# RgbwLedDriver.net
KiCad netlist of a schematic drawn in EAGLE
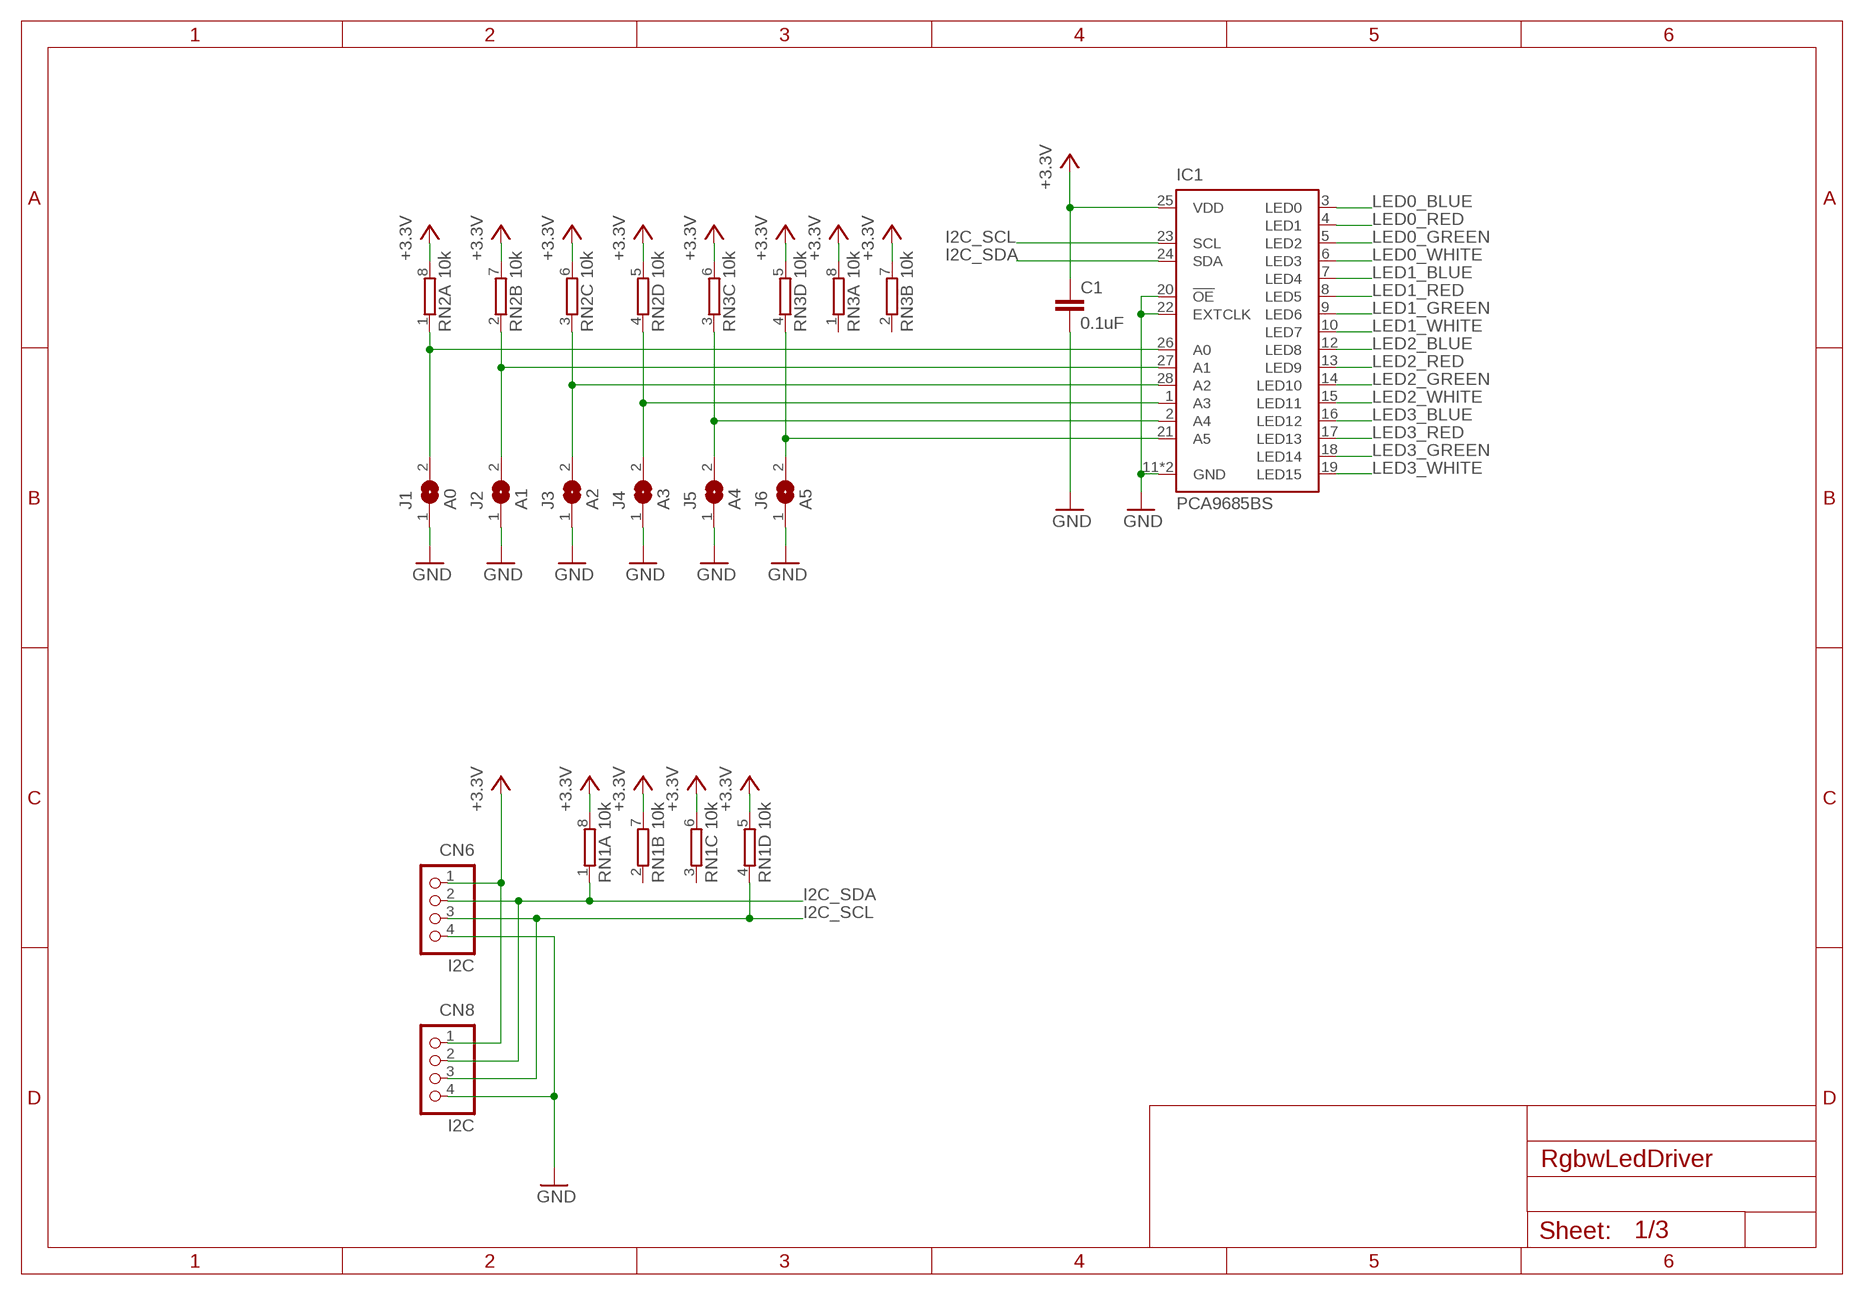
[diagram p0: schematic, sheet 1]
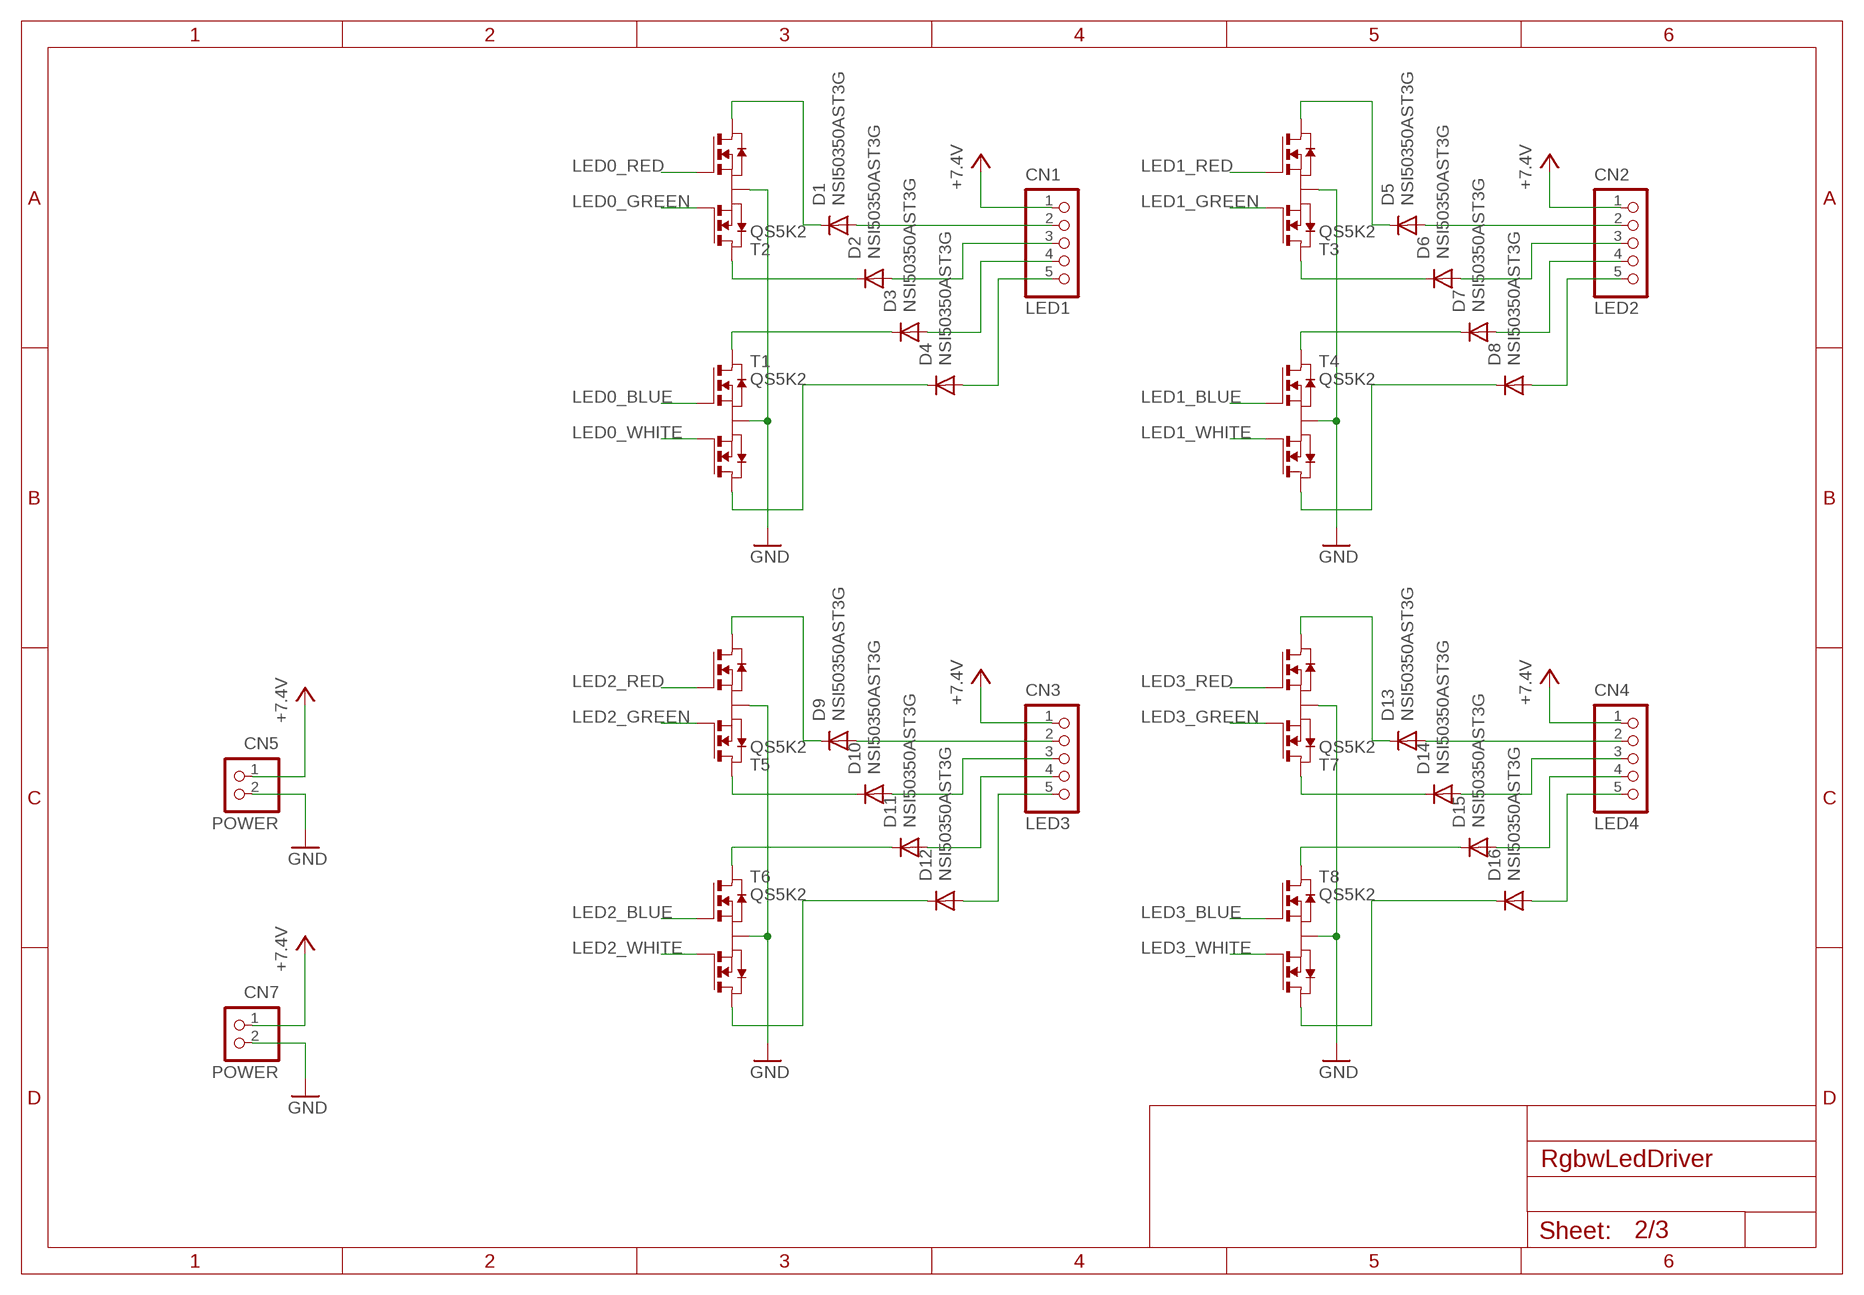
[diagram p1: schematic, sheet 2]
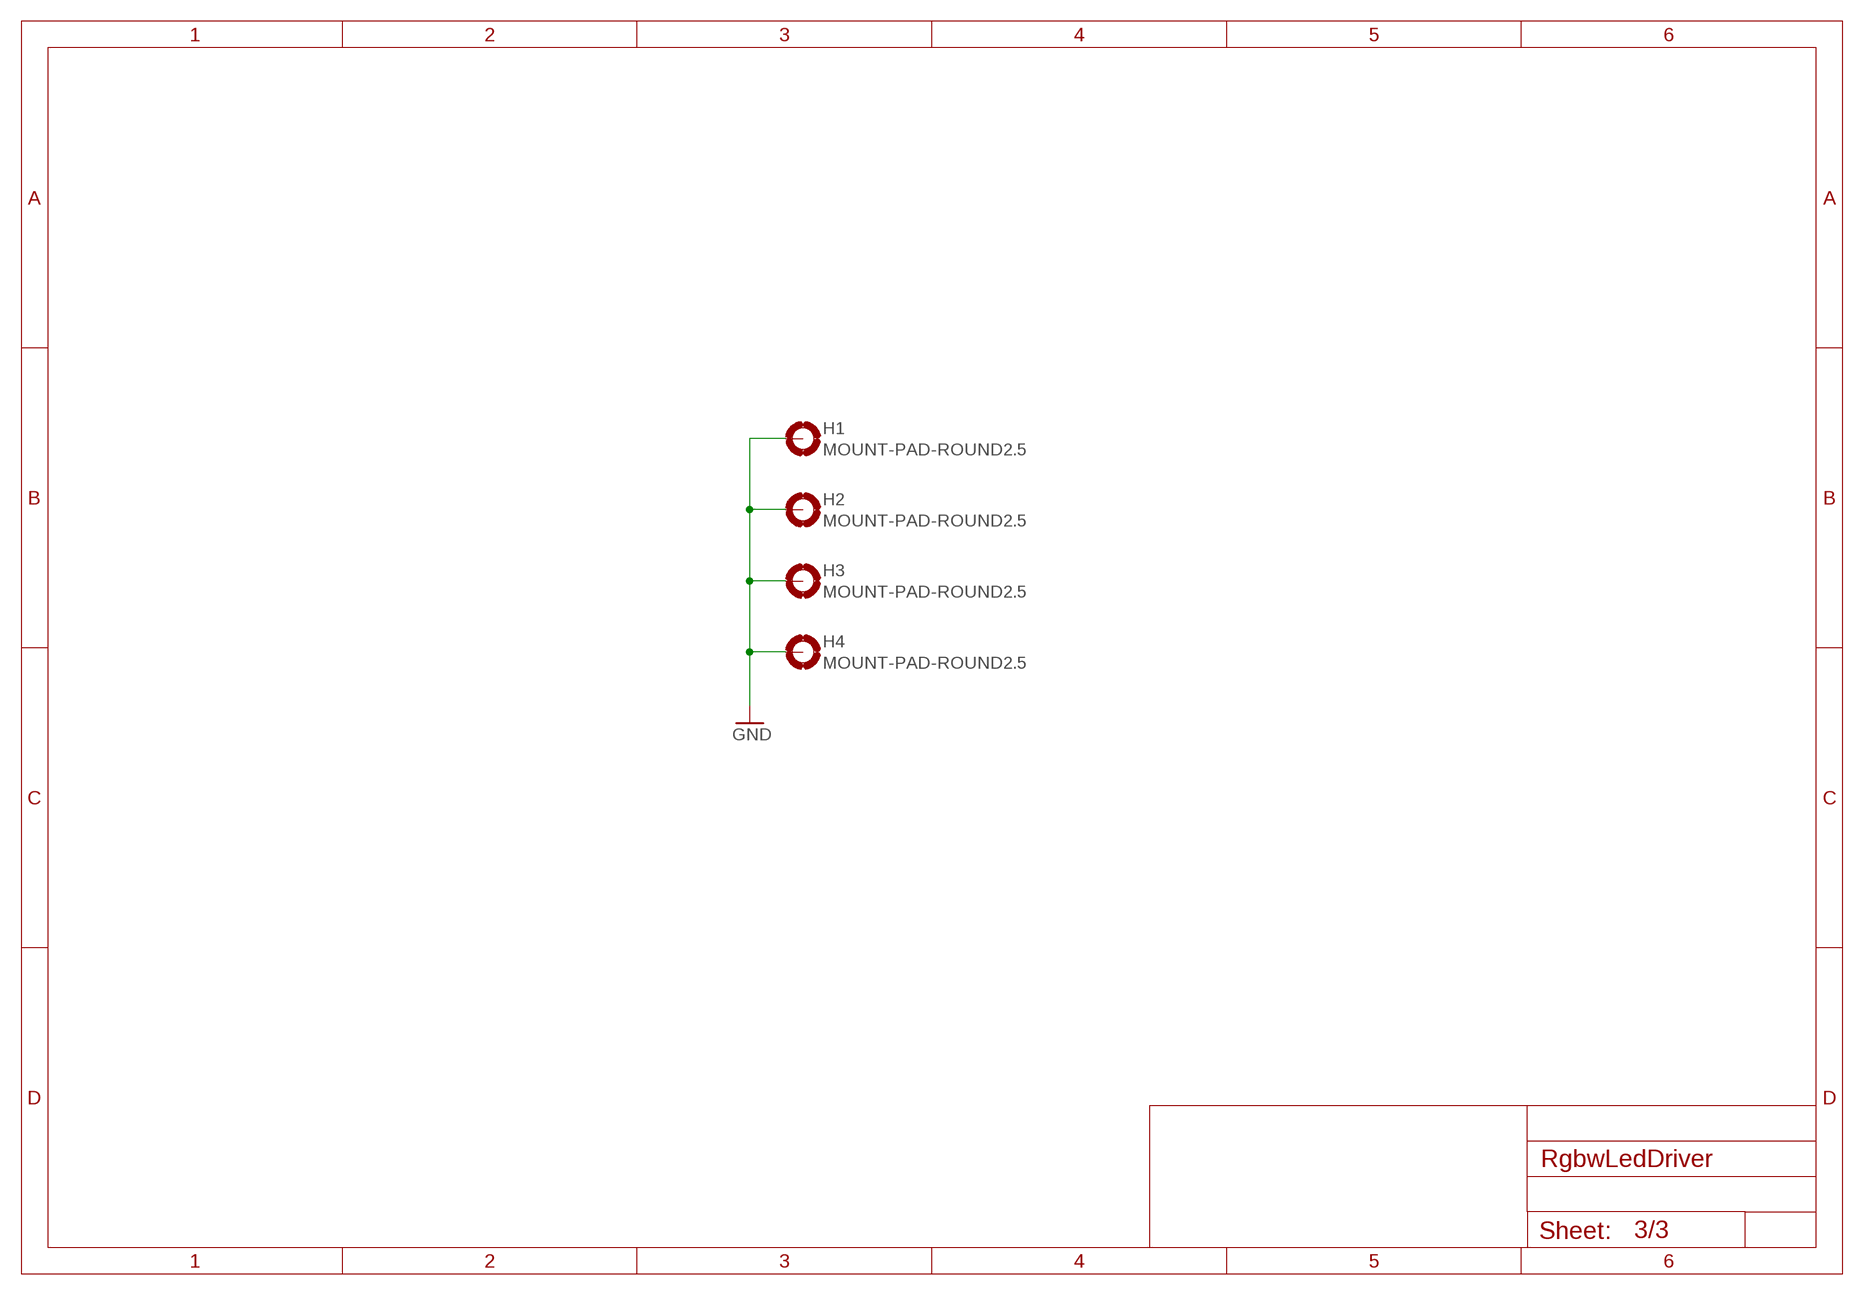
[diagram p2: schematic, sheet 3]

(export (version "E")
  (design (tool "Eeschema 10.0.6"))
  (components
    (comp (ref "CN1")
      (value "LED1")
      (footprint "eagle-import:S5B-PH-K-S")
      (libsource (lib "eagle-import") (part "S5B-PH-K-S"))
    )
    (comp (ref "CN2")
      (value "LED2")
      (footprint "eagle-import:S5B-PH-K-S")
      (libsource (lib "eagle-import") (part "S5B-PH-K-S"))
    )
    (comp (ref "CN3")
      (value "LED3")
      (footprint "eagle-import:S5B-PH-K-S")
      (libsource (lib "eagle-import") (part "S5B-PH-K-S"))
    )
    (comp (ref "CN4")
      (value "LED4")
      (footprint "eagle-import:S5B-PH-K-S")
      (libsource (lib "eagle-import") (part "S5B-PH-K-S"))
    )
    (comp (ref "CN5")
      (value "POWER")
      (footprint "eagle-import:B2P-VH")
      (libsource (lib "eagle-import") (part "B2P-VH"))
    )
    (comp (ref "CN7")
      (value "POWER")
      (footprint "eagle-import:B2P-VH")
      (libsource (lib "eagle-import") (part "B2P-VH"))
    )
    (comp (ref "D1")
      (value "NSI50350AST3G")
      (footprint "eagle-import:SMC")
      (libsource (lib "eagle-import") (part "NSI50350AST3G"))
    )
    (comp (ref "D2")
      (value "NSI50350AST3G")
      (footprint "eagle-import:SMC")
      (libsource (lib "eagle-import") (part "NSI50350AST3G"))
    )
    (comp (ref "D3")
      (value "NSI50350AST3G")
      (footprint "eagle-import:SMC")
      (libsource (lib "eagle-import") (part "NSI50350AST3G"))
    )
    (comp (ref "D4")
      (value "NSI50350AST3G")
      (footprint "eagle-import:SMC")
      (libsource (lib "eagle-import") (part "NSI50350AST3G"))
    )
    (comp (ref "D5")
      (value "NSI50350AST3G")
      (footprint "eagle-import:SMC")
      (libsource (lib "eagle-import") (part "NSI50350AST3G"))
    )
    (comp (ref "D6")
      (value "NSI50350AST3G")
      (footprint "eagle-import:SMC")
      (libsource (lib "eagle-import") (part "NSI50350AST3G"))
    )
    (comp (ref "D7")
      (value "NSI50350AST3G")
      (footprint "eagle-import:SMC")
      (libsource (lib "eagle-import") (part "NSI50350AST3G"))
    )
    (comp (ref "D8")
      (value "NSI50350AST3G")
      (footprint "eagle-import:SMC")
      (libsource (lib "eagle-import") (part "NSI50350AST3G"))
    )
    (comp (ref "D9")
      (value "NSI50350AST3G")
      (footprint "eagle-import:SMC")
      (libsource (lib "eagle-import") (part "NSI50350AST3G"))
    )
    (comp (ref "D10")
      (value "NSI50350AST3G")
      (footprint "eagle-import:SMC")
      (libsource (lib "eagle-import") (part "NSI50350AST3G"))
    )
    (comp (ref "D11")
      (value "NSI50350AST3G")
      (footprint "eagle-import:SMC")
      (libsource (lib "eagle-import") (part "NSI50350AST3G"))
    )
    (comp (ref "D12")
      (value "NSI50350AST3G")
      (footprint "eagle-import:SMC")
      (libsource (lib "eagle-import") (part "NSI50350AST3G"))
    )
    (comp (ref "D13")
      (value "NSI50350AST3G")
      (footprint "eagle-import:SMC")
      (libsource (lib "eagle-import") (part "NSI50350AST3G"))
    )
    (comp (ref "D14")
      (value "NSI50350AST3G")
      (footprint "eagle-import:SMC")
      (libsource (lib "eagle-import") (part "NSI50350AST3G"))
    )
    (comp (ref "D15")
      (value "NSI50350AST3G")
      (footprint "eagle-import:SMC")
      (libsource (lib "eagle-import") (part "NSI50350AST3G"))
    )
    (comp (ref "D16")
      (value "NSI50350AST3G")
      (footprint "eagle-import:SMC")
      (libsource (lib "eagle-import") (part "NSI50350AST3G"))
    )
    (comp (ref "T1")
      (value "QS5K2")
      (footprint "eagle-import:SOT23-5L")
      (libsource (lib "eagle-import") (part "QS5K2"))
    )
    (comp (ref "T2")
      (value "QS5K2")
      (footprint "eagle-import:SOT23-5L")
      (libsource (lib "eagle-import") (part "QS5K2"))
    )
    (comp (ref "T3")
      (value "QS5K2")
      (footprint "eagle-import:SOT23-5L")
      (libsource (lib "eagle-import") (part "QS5K2"))
    )
    (comp (ref "T4")
      (value "QS5K2")
      (footprint "eagle-import:SOT23-5L")
      (libsource (lib "eagle-import") (part "QS5K2"))
    )
    (comp (ref "T5")
      (value "QS5K2")
      (footprint "eagle-import:SOT23-5L")
      (libsource (lib "eagle-import") (part "QS5K2"))
    )
    (comp (ref "T6")
      (value "QS5K2")
      (footprint "eagle-import:SOT23-5L")
      (libsource (lib "eagle-import") (part "QS5K2"))
    )
    (comp (ref "T7")
      (value "QS5K2")
      (footprint "eagle-import:SOT23-5L")
      (libsource (lib "eagle-import") (part "QS5K2"))
    )
    (comp (ref "T8")
      (value "QS5K2")
      (footprint "eagle-import:SOT23-5L")
      (libsource (lib "eagle-import") (part "QS5K2"))
    )
    (comp (ref "H1")
      (value "MOUNT-PAD-ROUND2.5")
      (footprint "eagle-import:2,5-PAD")
      (libsource (lib "eagle-import") (part "MOUNT-PAD-ROUND2.5"))
    )
    (comp (ref "H2")
      (value "MOUNT-PAD-ROUND2.5")
      (footprint "eagle-import:2,5-PAD")
      (libsource (lib "eagle-import") (part "MOUNT-PAD-ROUND2.5"))
    )
    (comp (ref "H3")
      (value "MOUNT-PAD-ROUND2.5")
      (footprint "eagle-import:2,5-PAD")
      (libsource (lib "eagle-import") (part "MOUNT-PAD-ROUND2.5"))
    )
    (comp (ref "H4")
      (value "MOUNT-PAD-ROUND2.5")
      (footprint "eagle-import:2,5-PAD")
      (libsource (lib "eagle-import") (part "MOUNT-PAD-ROUND2.5"))
    )
    (comp (ref "C1")
      (value "0.1uF")
      (footprint "eagle-import:C0402")
      (libsource (lib "eagle-import") (part "C-EUC0402"))
    )
    (comp (ref "CN6")
      (value "I2C")
      (footprint "eagle-import:S4B-PH-K-S")
      (libsource (lib "eagle-import") (part "S4B-PH-K-S"))
    )
    (comp (ref "CN8")
      (value "I2C")
      (footprint "eagle-import:S4B-PH-K-S")
      (libsource (lib "eagle-import") (part "S4B-PH-K-S"))
    )
    (comp (ref "IC1")
      (value "PCA9685BS")
      (footprint "eagle-import:QFN28-ML_6X6MM")
      (libsource (lib "eagle-import") (part "PCA9685BS"))
    )
    (comp (ref "J1") (value "A0") (footprint "eagle-import:SJ") (libsource (lib "eagle-import") (part "SJ")))
    (comp (ref "J2") (value "A1") (footprint "eagle-import:SJ") (libsource (lib "eagle-import") (part "SJ")))
    (comp (ref "J3") (value "A2") (footprint "eagle-import:SJ") (libsource (lib "eagle-import") (part "SJ")))
    (comp (ref "J4") (value "A3") (footprint "eagle-import:SJ") (libsource (lib "eagle-import") (part "SJ")))
    (comp (ref "J5") (value "A4") (footprint "eagle-import:SJ") (libsource (lib "eagle-import") (part "SJ")))
    (comp (ref "J6") (value "A5") (footprint "eagle-import:SJ") (libsource (lib "eagle-import") (part "SJ")))
    (comp (ref "RN1")
      (value "10k")
      (footprint "eagle-import:EXB38V")
      (libsource (lib "eagle-import") (part "4R-NEXB38V"))
    )
    (comp (ref "RN2")
      (value "10k")
      (footprint "eagle-import:EXB38V")
      (libsource (lib "eagle-import") (part "4R-NEXB38V"))
    )
    (comp (ref "RN3")
      (value "10k")
      (footprint "eagle-import:EXB38V")
      (libsource (lib "eagle-import") (part "4R-NEXB38V"))
    )
  )
  (nets
    (net (code "1") (name "+3.3V") (class "Default")
      (node (ref "C1") (pin "1") (pinfunction "1_1") (pintype "passive"))
      (node (ref "CN6") (pin "1") (pinfunction "1_1") (pintype "passive"))
      (node (ref "CN8") (pin "1") (pinfunction "1_1") (pintype "passive"))
      (node (ref "IC1") (pin "25") (pinfunction "VDD_25") (pintype "power_in"))
      (node (ref "RN1") (pin "5") (pinfunction "2_5") (pintype "passive"))
      (node (ref "RN1") (pin "6") (pinfunction "2_6") (pintype "passive"))
      (node (ref "RN1") (pin "7") (pinfunction "2_7") (pintype "passive"))
      (node (ref "RN1") (pin "8") (pinfunction "2_8") (pintype "passive"))
      (node (ref "RN2") (pin "5") (pinfunction "2_5") (pintype "passive"))
      (node (ref "RN2") (pin "6") (pinfunction "2_6") (pintype "passive"))
      (node (ref "RN2") (pin "7") (pinfunction "2_7") (pintype "passive"))
      (node (ref "RN2") (pin "8") (pinfunction "2_8") (pintype "passive"))
      (node (ref "RN3") (pin "5") (pinfunction "2_5") (pintype "passive"))
      (node (ref "RN3") (pin "6") (pinfunction "2_6") (pintype "passive"))
      (node (ref "RN3") (pin "7") (pinfunction "2_7") (pintype "passive"))
      (node (ref "RN3") (pin "8") (pinfunction "2_8") (pintype "passive"))
    )
    (net (code "2") (name "+7.4V") (class "Default")
      (node (ref "CN1") (pin "1") (pinfunction "1_1") (pintype "passive"))
      (node (ref "CN2") (pin "1") (pinfunction "1_1") (pintype "passive"))
      (node (ref "CN3") (pin "1") (pinfunction "1_1") (pintype "passive"))
      (node (ref "CN4") (pin "1") (pinfunction "1_1") (pintype "passive"))
      (node (ref "CN5") (pin "1") (pinfunction "1_1") (pintype "passive"))
      (node (ref "CN7") (pin "1") (pinfunction "1_1") (pintype "passive"))
    )
    (net (code "3") (name "GND") (class "Default")
      (node (ref "C1") (pin "2") (pinfunction "2_2") (pintype "passive"))
      (node (ref "CN5") (pin "2") (pinfunction "2_2") (pintype "passive"))
      (node (ref "CN6") (pin "4") (pinfunction "4_4") (pintype "passive"))
      (node (ref "CN7") (pin "2") (pinfunction "2_2") (pintype "passive"))
      (node (ref "CN8") (pin "4") (pinfunction "4_4") (pintype "passive"))
      (node (ref "H1") (pin "B2,5") (pinfunction "MOUNT_B2,5") (pintype "passive"))
      (node (ref "H2") (pin "B2,5") (pinfunction "MOUNT_B2,5") (pintype "passive"))
      (node (ref "H3") (pin "B2,5") (pinfunction "MOUNT_B2,5") (pintype "passive"))
      (node (ref "H4") (pin "B2,5") (pinfunction "MOUNT_B2,5") (pintype "passive"))
      (node (ref "IC1") (pin "11") (pinfunction "GND_11") (pintype "power_in"))
      (node (ref "IC1") (pin "20") (pinfunction "~{OE}_20") (pintype "input"))
      (node (ref "IC1") (pin "22") (pinfunction "EXTCLK_22") (pintype "input"))
      (node (ref "IC1") (pin "EXP") (pinfunction "GND_EXP") (pintype "power_in"))
      (node (ref "J1") (pin "1") (pinfunction "1_1") (pintype "passive"))
      (node (ref "J2") (pin "1") (pinfunction "1_1") (pintype "passive"))
      (node (ref "J3") (pin "1") (pinfunction "1_1") (pintype "passive"))
      (node (ref "J4") (pin "1") (pinfunction "1_1") (pintype "passive"))
      (node (ref "J5") (pin "1") (pinfunction "1_1") (pintype "passive"))
      (node (ref "J6") (pin "1") (pinfunction "1_1") (pintype "passive"))
      (node (ref "T1") (pin "2") (pinfunction "S_2") (pintype "passive"))
      (node (ref "T2") (pin "2") (pinfunction "S_2") (pintype "passive"))
      (node (ref "T3") (pin "2") (pinfunction "S_2") (pintype "passive"))
      (node (ref "T4") (pin "2") (pinfunction "S_2") (pintype "passive"))
      (node (ref "T5") (pin "2") (pinfunction "S_2") (pintype "passive"))
      (node (ref "T6") (pin "2") (pinfunction "S_2") (pintype "passive"))
      (node (ref "T7") (pin "2") (pinfunction "S_2") (pintype "passive"))
      (node (ref "T8") (pin "2") (pinfunction "S_2") (pintype "passive"))
    )
    (net (code "4") (name "I2C_SCL") (class "Default")
      (node (ref "CN6") (pin "3") (pinfunction "3_3") (pintype "passive"))
      (node (ref "CN8") (pin "3") (pinfunction "3_3") (pintype "passive"))
      (node (ref "IC1") (pin "23") (pinfunction "SCL_23") (pintype "input"))
      (node (ref "RN1") (pin "4") (pinfunction "1_4") (pintype "passive"))
    )
    (net (code "5") (name "I2C_SDA") (class "Default")
      (node (ref "CN6") (pin "2") (pinfunction "2_2") (pintype "passive"))
      (node (ref "CN8") (pin "2") (pinfunction "2_2") (pintype "passive"))
      (node (ref "IC1") (pin "24") (pinfunction "SDA_24") (pintype "bidirectional"))
      (node (ref "RN1") (pin "1") (pinfunction "1_1") (pintype "passive"))
    )
    (net (code "6") (name "LED0_BLUE") (class "Default")
      (node (ref "IC1") (pin "3") (pinfunction "LED0_3") (pintype "output"))
      (node (ref "T1") (pin "1") (pinfunction "G1_1") (pintype "passive"))
    )
    (net (code "7") (name "LED0_GREEN") (class "Default")
      (node (ref "IC1") (pin "5") (pinfunction "LED2_5") (pintype "output"))
      (node (ref "T2") (pin "1") (pinfunction "G1_1") (pintype "passive"))
    )
    (net (code "8") (name "LED0_RED") (class "Default")
      (node (ref "IC1") (pin "4") (pinfunction "LED1_4") (pintype "output"))
      (node (ref "T2") (pin "3") (pinfunction "G2_3") (pintype "passive"))
    )
    (net (code "9") (name "LED0_WHITE") (class "Default")
      (node (ref "IC1") (pin "6") (pinfunction "LED3_6") (pintype "output"))
      (node (ref "T1") (pin "3") (pinfunction "G2_3") (pintype "passive"))
    )
    (net (code "10") (name "LED1_BLUE") (class "Default")
      (node (ref "IC1") (pin "7") (pinfunction "LED4_7") (pintype "output"))
      (node (ref "T4") (pin "1") (pinfunction "G1_1") (pintype "passive"))
    )
    (net (code "11") (name "LED1_GREEN") (class "Default")
      (node (ref "IC1") (pin "9") (pinfunction "LED6_9") (pintype "output"))
      (node (ref "T3") (pin "1") (pinfunction "G1_1") (pintype "passive"))
    )
    (net (code "12") (name "LED1_RED") (class "Default")
      (node (ref "IC1") (pin "8") (pinfunction "LED5_8") (pintype "output"))
      (node (ref "T3") (pin "3") (pinfunction "G2_3") (pintype "passive"))
    )
    (net (code "13") (name "LED1_WHITE") (class "Default")
      (node (ref "IC1") (pin "10") (pinfunction "LED7_10") (pintype "output"))
      (node (ref "T4") (pin "3") (pinfunction "G2_3") (pintype "passive"))
    )
    (net (code "14") (name "LED2_BLUE") (class "Default")
      (node (ref "IC1") (pin "12") (pinfunction "LED8_12") (pintype "output"))
      (node (ref "T6") (pin "1") (pinfunction "G1_1") (pintype "passive"))
    )
    (net (code "15") (name "LED2_GREEN") (class "Default")
      (node (ref "IC1") (pin "14") (pinfunction "LED10_14") (pintype "output"))
      (node (ref "T5") (pin "1") (pinfunction "G1_1") (pintype "passive"))
    )
    (net (code "16") (name "LED2_RED") (class "Default")
      (node (ref "IC1") (pin "13") (pinfunction "LED9_13") (pintype "output"))
      (node (ref "T5") (pin "3") (pinfunction "G2_3") (pintype "passive"))
    )
    (net (code "17") (name "LED2_WHITE") (class "Default")
      (node (ref "IC1") (pin "15") (pinfunction "LED11_15") (pintype "output"))
      (node (ref "T6") (pin "3") (pinfunction "G2_3") (pintype "passive"))
    )
    (net (code "18") (name "LED3_BLUE") (class "Default")
      (node (ref "IC1") (pin "16") (pinfunction "LED12_16") (pintype "output"))
      (node (ref "T8") (pin "1") (pinfunction "G1_1") (pintype "passive"))
    )
    (net (code "19") (name "LED3_GREEN") (class "Default")
      (node (ref "IC1") (pin "18") (pinfunction "LED14_18") (pintype "output"))
      (node (ref "T7") (pin "1") (pinfunction "G1_1") (pintype "passive"))
    )
    (net (code "20") (name "LED3_RED") (class "Default")
      (node (ref "IC1") (pin "17") (pinfunction "LED13_17") (pintype "output"))
      (node (ref "T7") (pin "3") (pinfunction "G2_3") (pintype "passive"))
    )
    (net (code "21") (name "LED3_WHITE") (class "Default")
      (node (ref "IC1") (pin "19") (pinfunction "LED15_19") (pintype "output"))
      (node (ref "T8") (pin "3") (pinfunction "G2_3") (pintype "passive"))
    )
    (net (code "22") (name "Net-(CN1-Pad2)") (class "Default")
      (node (ref "CN1") (pin "2") (pinfunction "2_2") (pintype "passive"))
      (node (ref "D1") (pin "A") (pinfunction "A_A") (pintype "passive"))
    )
    (net (code "23") (name "Net-(CN1-Pad3)") (class "Default")
      (node (ref "CN1") (pin "3") (pinfunction "3_3") (pintype "passive"))
      (node (ref "D2") (pin "A") (pinfunction "A_A") (pintype "passive"))
    )
    (net (code "24") (name "Net-(CN1-Pad4)") (class "Default")
      (node (ref "CN1") (pin "4") (pinfunction "4_4") (pintype "passive"))
      (node (ref "D3") (pin "A") (pinfunction "A_A") (pintype "passive"))
    )
    (net (code "25") (name "Net-(CN1-Pad5)") (class "Default")
      (node (ref "CN1") (pin "5") (pinfunction "5_5") (pintype "passive"))
      (node (ref "D4") (pin "A") (pinfunction "A_A") (pintype "passive"))
    )
    (net (code "26") (name "Net-(CN2-Pad2)") (class "Default")
      (node (ref "CN2") (pin "2") (pinfunction "2_2") (pintype "passive"))
      (node (ref "D5") (pin "A") (pinfunction "A_A") (pintype "passive"))
    )
    (net (code "27") (name "Net-(CN2-Pad3)") (class "Default")
      (node (ref "CN2") (pin "3") (pinfunction "3_3") (pintype "passive"))
      (node (ref "D6") (pin "A") (pinfunction "A_A") (pintype "passive"))
    )
    (net (code "28") (name "Net-(CN2-Pad4)") (class "Default")
      (node (ref "CN2") (pin "4") (pinfunction "4_4") (pintype "passive"))
      (node (ref "D7") (pin "A") (pinfunction "A_A") (pintype "passive"))
    )
    (net (code "29") (name "Net-(CN2-Pad5)") (class "Default")
      (node (ref "CN2") (pin "5") (pinfunction "5_5") (pintype "passive"))
      (node (ref "D8") (pin "A") (pinfunction "A_A") (pintype "passive"))
    )
    (net (code "30") (name "Net-(CN3-Pad2)") (class "Default")
      (node (ref "CN3") (pin "2") (pinfunction "2_2") (pintype "passive"))
      (node (ref "D9") (pin "A") (pinfunction "A_A") (pintype "passive"))
    )
    (net (code "31") (name "Net-(CN3-Pad3)") (class "Default")
      (node (ref "CN3") (pin "3") (pinfunction "3_3") (pintype "passive"))
      (node (ref "D10") (pin "A") (pinfunction "A_A") (pintype "passive"))
    )
    (net (code "32") (name "Net-(CN3-Pad4)") (class "Default")
      (node (ref "CN3") (pin "4") (pinfunction "4_4") (pintype "passive"))
      (node (ref "D11") (pin "A") (pinfunction "A_A") (pintype "passive"))
    )
    (net (code "33") (name "Net-(CN3-Pad5)") (class "Default")
      (node (ref "CN3") (pin "5") (pinfunction "5_5") (pintype "passive"))
      (node (ref "D12") (pin "A") (pinfunction "A_A") (pintype "passive"))
    )
    (net (code "34") (name "Net-(CN4-Pad2)") (class "Default")
      (node (ref "CN4") (pin "2") (pinfunction "2_2") (pintype "passive"))
      (node (ref "D13") (pin "A") (pinfunction "A_A") (pintype "passive"))
    )
    (net (code "35") (name "Net-(CN4-Pad3)") (class "Default")
      (node (ref "CN4") (pin "3") (pinfunction "3_3") (pintype "passive"))
      (node (ref "D14") (pin "A") (pinfunction "A_A") (pintype "passive"))
    )
    (net (code "36") (name "Net-(CN4-Pad4)") (class "Default")
      (node (ref "CN4") (pin "4") (pinfunction "4_4") (pintype "passive"))
      (node (ref "D15") (pin "A") (pinfunction "A_A") (pintype "passive"))
    )
    (net (code "37") (name "Net-(CN4-Pad5)") (class "Default")
      (node (ref "CN4") (pin "5") (pinfunction "5_5") (pintype "passive"))
      (node (ref "D16") (pin "A") (pinfunction "A_A") (pintype "passive"))
    )
    (net (code "38") (name "Net-(IC1-A0)") (class "Default")
      (node (ref "IC1") (pin "26") (pinfunction "A0_26") (pintype "input"))
      (node (ref "J1") (pin "2") (pinfunction "2_2") (pintype "passive"))
      (node (ref "RN2") (pin "1") (pinfunction "1_1") (pintype "passive"))
    )
    (net (code "39") (name "Net-(IC1-A1)") (class "Default")
      (node (ref "IC1") (pin "27") (pinfunction "A1_27") (pintype "input"))
      (node (ref "J2") (pin "2") (pinfunction "2_2") (pintype "passive"))
      (node (ref "RN2") (pin "2") (pinfunction "1_2") (pintype "passive"))
    )
    (net (code "40") (name "Net-(IC1-A2)") (class "Default")
      (node (ref "IC1") (pin "28") (pinfunction "A2_28") (pintype "input"))
      (node (ref "J3") (pin "2") (pinfunction "2_2") (pintype "passive"))
      (node (ref "RN2") (pin "3") (pinfunction "1_3") (pintype "passive"))
    )
    (net (code "41") (name "Net-(IC1-A3)") (class "Default")
      (node (ref "IC1") (pin "1") (pinfunction "A3_1") (pintype "input"))
      (node (ref "J4") (pin "2") (pinfunction "2_2") (pintype "passive"))
      (node (ref "RN2") (pin "4") (pinfunction "1_4") (pintype "passive"))
    )
    (net (code "42") (name "Net-(IC1-A4)") (class "Default")
      (node (ref "IC1") (pin "2") (pinfunction "A4_2") (pintype "input"))
      (node (ref "J5") (pin "2") (pinfunction "2_2") (pintype "passive"))
      (node (ref "RN3") (pin "3") (pinfunction "1_3") (pintype "passive"))
    )
    (net (code "43") (name "Net-(IC1-A5)") (class "Default")
      (node (ref "IC1") (pin "21") (pinfunction "A5_21") (pintype "input"))
      (node (ref "J6") (pin "2") (pinfunction "2_2") (pintype "passive"))
      (node (ref "RN3") (pin "4") (pinfunction "1_4") (pintype "passive"))
    )
    (net (code "44") (name "Net-(T1-D1)") (class "Default")
      (node (ref "D3") (pin "C") (pinfunction "C_C") (pintype "passive"))
      (node (ref "T1") (pin "5") (pinfunction "D1_5") (pintype "passive"))
    )
    (net (code "45") (name "Net-(T1-D2)") (class "Default")
      (node (ref "D4") (pin "C") (pinfunction "C_C") (pintype "passive"))
      (node (ref "T1") (pin "4") (pinfunction "D2_4") (pintype "passive"))
    )
    (net (code "46") (name "Net-(T2-D1)") (class "Default")
      (node (ref "D2") (pin "C") (pinfunction "C_C") (pintype "passive"))
      (node (ref "T2") (pin "5") (pinfunction "D1_5") (pintype "passive"))
    )
    (net (code "47") (name "Net-(T2-D2)") (class "Default")
      (node (ref "D1") (pin "C") (pinfunction "C_C") (pintype "passive"))
      (node (ref "T2") (pin "4") (pinfunction "D2_4") (pintype "passive"))
    )
    (net (code "48") (name "Net-(T3-D1)") (class "Default")
      (node (ref "D6") (pin "C") (pinfunction "C_C") (pintype "passive"))
      (node (ref "T3") (pin "5") (pinfunction "D1_5") (pintype "passive"))
    )
    (net (code "49") (name "Net-(T3-D2)") (class "Default")
      (node (ref "D5") (pin "C") (pinfunction "C_C") (pintype "passive"))
      (node (ref "T3") (pin "4") (pinfunction "D2_4") (pintype "passive"))
    )
    (net (code "50") (name "Net-(T4-D1)") (class "Default")
      (node (ref "D7") (pin "C") (pinfunction "C_C") (pintype "passive"))
      (node (ref "T4") (pin "5") (pinfunction "D1_5") (pintype "passive"))
    )
    (net (code "51") (name "Net-(T4-D2)") (class "Default")
      (node (ref "D8") (pin "C") (pinfunction "C_C") (pintype "passive"))
      (node (ref "T4") (pin "4") (pinfunction "D2_4") (pintype "passive"))
    )
    (net (code "52") (name "Net-(T5-D1)") (class "Default")
      (node (ref "D10") (pin "C") (pinfunction "C_C") (pintype "passive"))
      (node (ref "T5") (pin "5") (pinfunction "D1_5") (pintype "passive"))
    )
    (net (code "53") (name "Net-(T5-D2)") (class "Default")
      (node (ref "D9") (pin "C") (pinfunction "C_C") (pintype "passive"))
      (node (ref "T5") (pin "4") (pinfunction "D2_4") (pintype "passive"))
    )
    (net (code "54") (name "Net-(T6-D1)") (class "Default")
      (node (ref "D11") (pin "C") (pinfunction "C_C") (pintype "passive"))
      (node (ref "T6") (pin "5") (pinfunction "D1_5") (pintype "passive"))
    )
    (net (code "55") (name "Net-(T6-D2)") (class "Default")
      (node (ref "D12") (pin "C") (pinfunction "C_C") (pintype "passive"))
      (node (ref "T6") (pin "4") (pinfunction "D2_4") (pintype "passive"))
    )
    (net (code "56") (name "Net-(T7-D1)") (class "Default")
      (node (ref "D14") (pin "C") (pinfunction "C_C") (pintype "passive"))
      (node (ref "T7") (pin "5") (pinfunction "D1_5") (pintype "passive"))
    )
    (net (code "57") (name "Net-(T7-D2)") (class "Default")
      (node (ref "D13") (pin "C") (pinfunction "C_C") (pintype "passive"))
      (node (ref "T7") (pin "4") (pinfunction "D2_4") (pintype "passive"))
    )
    (net (code "58") (name "Net-(T8-D1)") (class "Default")
      (node (ref "D15") (pin "C") (pinfunction "C_C") (pintype "passive"))
      (node (ref "T8") (pin "5") (pinfunction "D1_5") (pintype "passive"))
    )
    (net (code "59") (name "Net-(T8-D2)") (class "Default")
      (node (ref "D16") (pin "C") (pinfunction "C_C") (pintype "passive"))
      (node (ref "T8") (pin "4") (pinfunction "D2_4") (pintype "passive"))
    )
    (net (code "60") (name "unconnected-(RN1B-1-Pad2)") (class "Default")
      (node (ref "RN1") (pin "2") (pinfunction "1_2") (pintype "passive"))
    )
    (net (code "61") (name "unconnected-(RN1C-1-Pad3)") (class "Default")
      (node (ref "RN1") (pin "3") (pinfunction "1_3") (pintype "passive"))
    )
    (net (code "62") (name "unconnected-(RN3-Pad1)") (class "Default")
      (node (ref "RN3") (pin "1") (pinfunction "1_1") (pintype "passive"))
    )
    (net (code "63") (name "unconnected-(RN3B-1-Pad2)") (class "Default")
      (node (ref "RN3") (pin "2") (pinfunction "1_2") (pintype "passive"))
    )
  )
)
